# Weather_Station_For_Drones_-_MKR1000.net
KiCad netlist of a schematic drawn in EAGLE
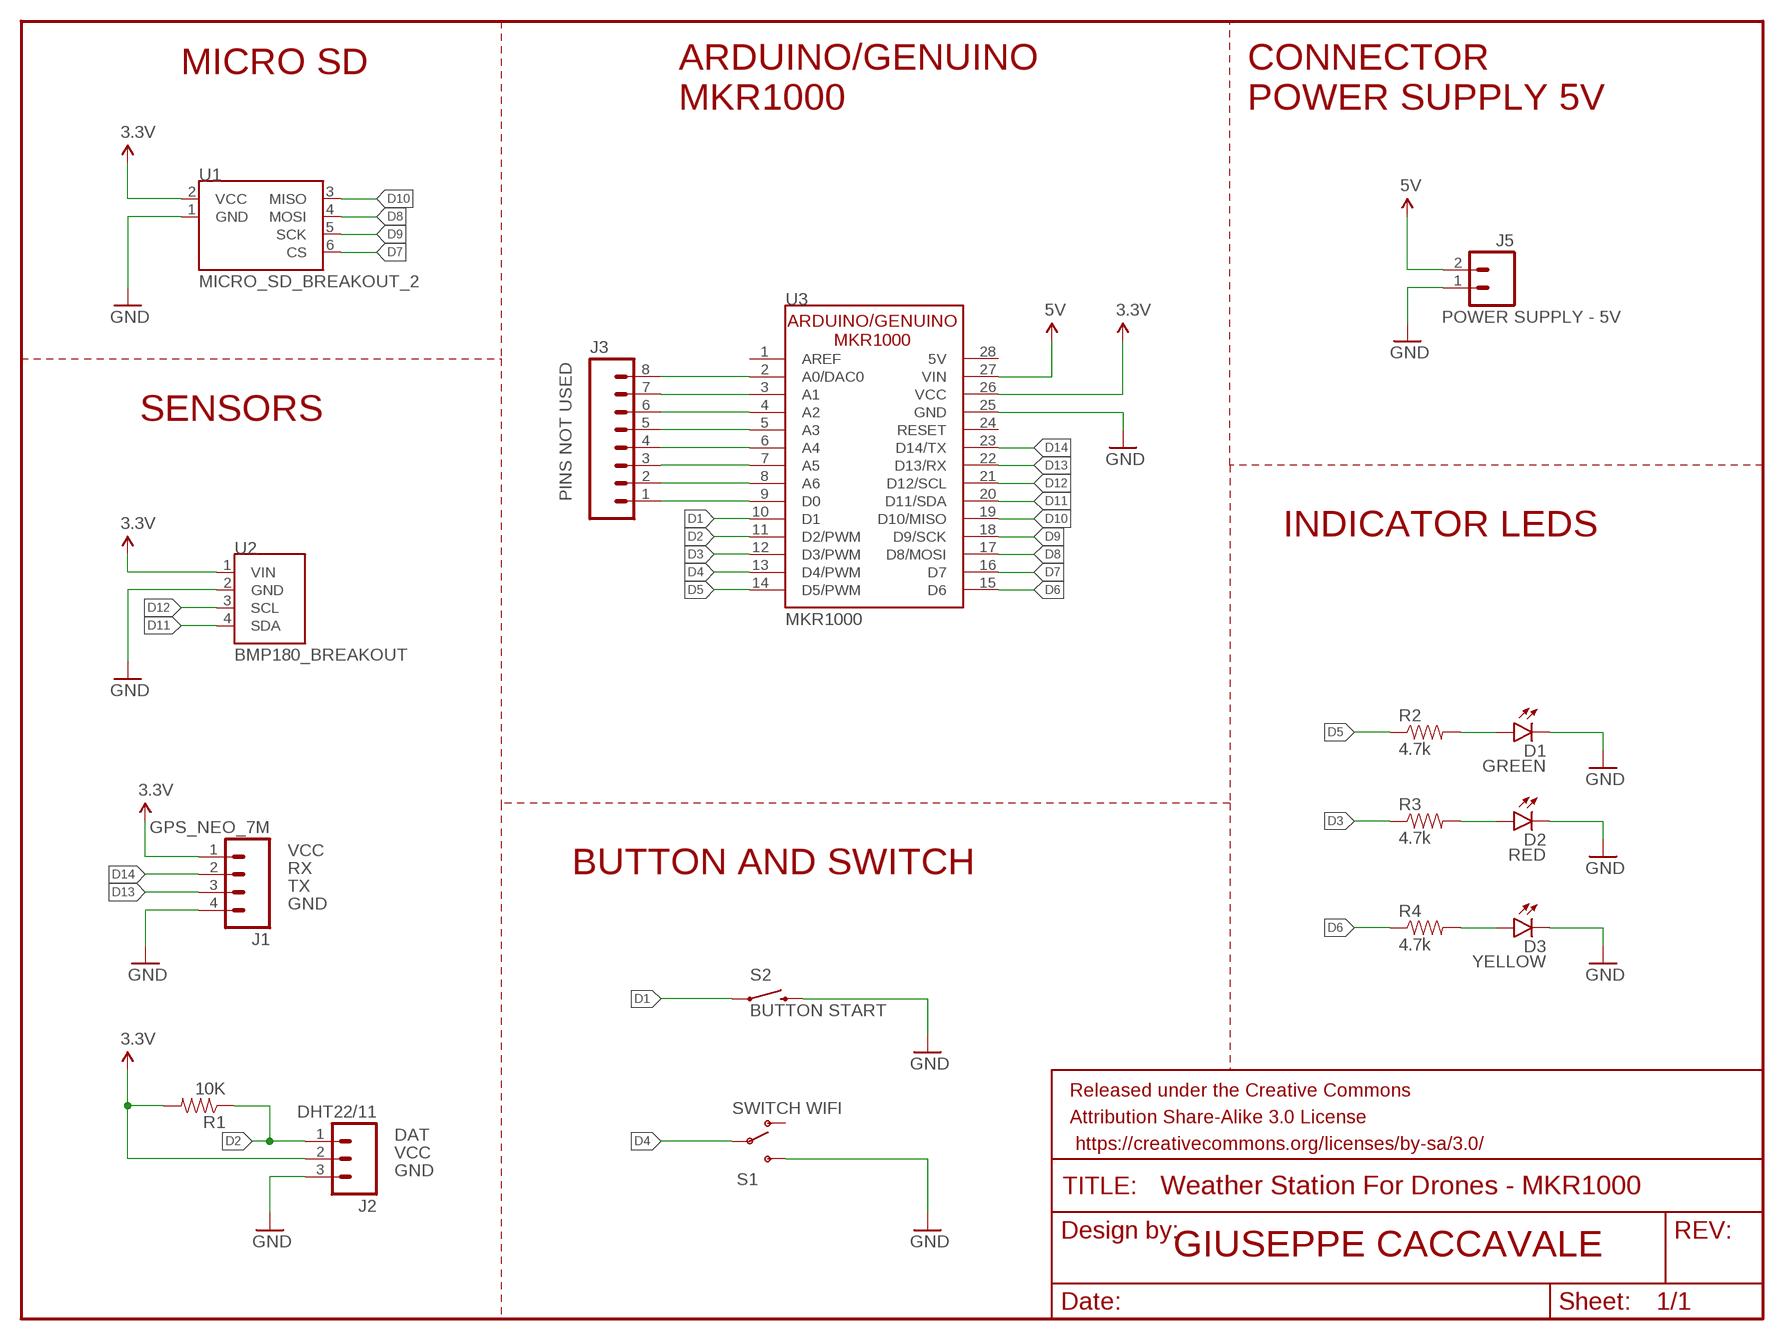
[diagram p0: schematic, sheet 1]

(export (version "E")
  (design (tool "Eeschema 10.0.6"))
  (components
    (comp (ref "D1")
      (value "GREEN")
      (footprint "eagle-import:LED3MM")
      (libsource (lib "eagle-import") (part "LED3MM"))
    )
    (comp (ref "D2")
      (value "RED")
      (footprint "eagle-import:LED3MM")
      (libsource (lib "eagle-import") (part "LED3MM"))
    )
    (comp (ref "D3")
      (value "YELLOW")
      (footprint "eagle-import:LED3MM")
      (libsource (lib "eagle-import") (part "LED3MM"))
    )
    (comp (ref "FRAME1")
      (value "FRAME-LETTER")
      (footprint "eagle-import:CREATIVE_COMMONS")
      (libsource (lib "eagle-import") (part "FRAME-LETTER"))
    )
    (comp (ref "J1")
      (value "GPS_NEO_7M")
      (footprint "eagle-import:1X04_LONGPADS")
      (libsource (lib "eagle-import") (part "M04LONGPADS"))
    )
    (comp (ref "J2")
      (value "DHT22/11")
      (footprint "eagle-import:1X03_LONGPADS")
      (libsource (lib "eagle-import") (part "M03LONGPADS"))
    )
    (comp (ref "J3")
      (value "PINS NOT USED")
      (footprint "eagle-import:1X08_LONGPADS")
      (libsource (lib "eagle-import") (part "M08LONGPADS"))
    )
    (comp (ref "J5")
      (value "POWER SUPPLY - 5V")
      (footprint "eagle-import:JST-2-PTH")
      (libsource (lib "eagle-import") (part "M02JST-PTH-2"))
    )
    (comp (ref "R1")
      (value "10K")
      (footprint "eagle-import:AXIAL-0.3")
      (libsource (lib "eagle-import") (part "RESISTORAXIAL-0.3"))
    )
    (comp (ref "R2")
      (value "4.7k")
      (footprint "eagle-import:AXIAL-0.3")
      (libsource (lib "eagle-import") (part "RESISTORAXIAL-0.3"))
    )
    (comp (ref "R3")
      (value "4.7k")
      (footprint "eagle-import:AXIAL-0.3")
      (libsource (lib "eagle-import") (part "RESISTORAXIAL-0.3"))
    )
    (comp (ref "R4")
      (value "4.7k")
      (footprint "eagle-import:AXIAL-0.3")
      (libsource (lib "eagle-import") (part "RESISTORAXIAL-0.3"))
    )
    (comp (ref "S1")
      (value "SWITCH WIFI")
      (footprint "eagle-import:SWITCH-SPDT_KIT")
      (libsource (lib "eagle-import") (part "SWITCH-SPDTKIT"))
    )
    (comp (ref "S2")
      (value "BUTTON START")
      (footprint "eagle-import:TACTILE-PTH")
      (libsource (lib "eagle-import") (part "SWITCH-MOMENTARY-2PTH"))
    )
    (comp (ref "U1")
      (value "MICRO_SD_BREAKOUT_2")
      (footprint "eagle-import:MICRO_SD_ONLY_PIN")
      (libsource (lib "eagle-import") (part "MICRO_SD_BREAKOUT_2"))
    )
    (comp (ref "U2")
      (value "BMP180_BREAKOUT")
      (footprint "eagle-import:BMP180_BREAKOUT")
      (libsource (lib "eagle-import") (part "BMP180_BREAKOUT"))
    )
    (comp (ref "U3")
      (value "MKR1000")
      (footprint "eagle-import:MKR1000")
      (libsource (lib "eagle-import") (part "MKR1000"))
    )
  )
  (nets
    (net (code "1") (name "3.3V") (class "Default")
      (node (ref "J1") (pin "1") (pinfunction "1_1") (pintype "passive"))
      (node (ref "J2") (pin "2") (pinfunction "2_2") (pintype "passive"))
      (node (ref "R1") (pin "P$2") (pinfunction "2_P$2") (pintype "passive"))
      (node (ref "U1") (pin "2") (pinfunction "VCC_2") (pintype "bidirectional"))
      (node (ref "U2") (pin "1") (pinfunction "VIN_1") (pintype "bidirectional"))
      (node (ref "U3") (pin "26") (pinfunction "VCC_26") (pintype "bidirectional"))
    )
    (net (code "2") (name "5V") (class "Default")
      (node (ref "J5") (pin "2") (pinfunction "2_2") (pintype "passive"))
      (node (ref "U3") (pin "27") (pinfunction "VIN_27") (pintype "bidirectional"))
    )
    (net (code "3") (name "D1") (class "Default")
      (node (ref "S2") (pin "1") (pinfunction "1_1") (pintype "passive"))
      (node (ref "S2") (pin "2") (pinfunction "1_2") (pintype "passive"))
      (node (ref "U3") (pin "10") (pinfunction "D1_10") (pintype "bidirectional"))
    )
    (net (code "4") (name "D2") (class "Default")
      (node (ref "J2") (pin "1") (pinfunction "1_1") (pintype "passive"))
      (node (ref "R1") (pin "P$1") (pinfunction "1_P$1") (pintype "passive"))
      (node (ref "U3") (pin "11") (pinfunction "D2/PWM_11") (pintype "bidirectional"))
    )
    (net (code "5") (name "D3") (class "Default")
      (node (ref "R3") (pin "P$1") (pinfunction "1_P$1") (pintype "passive"))
      (node (ref "U3") (pin "12") (pinfunction "D3/PWM_12") (pintype "bidirectional"))
    )
    (net (code "6") (name "D4") (class "Default")
      (node (ref "S1") (pin "2") (pinfunction "P_2") (pintype "passive"))
      (node (ref "U3") (pin "13") (pinfunction "D4/PWM_13") (pintype "bidirectional"))
    )
    (net (code "7") (name "D5") (class "Default")
      (node (ref "R2") (pin "P$1") (pinfunction "1_P$1") (pintype "passive"))
      (node (ref "U3") (pin "14") (pinfunction "D5/PWM_14") (pintype "bidirectional"))
    )
    (net (code "8") (name "D6") (class "Default")
      (node (ref "R4") (pin "P$1") (pinfunction "1_P$1") (pintype "passive"))
      (node (ref "U3") (pin "15") (pinfunction "D6_15") (pintype "bidirectional"))
    )
    (net (code "9") (name "D7") (class "Default")
      (node (ref "U1") (pin "6") (pinfunction "CS_6") (pintype "bidirectional"))
      (node (ref "U3") (pin "16") (pinfunction "D7_16") (pintype "bidirectional"))
    )
    (net (code "10") (name "D8") (class "Default")
      (node (ref "U1") (pin "4") (pinfunction "MOSI_4") (pintype "bidirectional"))
      (node (ref "U3") (pin "17") (pinfunction "D8/MOSI_17") (pintype "bidirectional"))
    )
    (net (code "11") (name "D9") (class "Default")
      (node (ref "U1") (pin "5") (pinfunction "SCK_5") (pintype "bidirectional"))
      (node (ref "U3") (pin "18") (pinfunction "D9/SCK_18") (pintype "bidirectional"))
    )
    (net (code "12") (name "D10") (class "Default")
      (node (ref "U1") (pin "3") (pinfunction "MISO_3") (pintype "bidirectional"))
      (node (ref "U3") (pin "19") (pinfunction "D10/MISO_19") (pintype "bidirectional"))
    )
    (net (code "13") (name "D11") (class "Default")
      (node (ref "U2") (pin "4") (pinfunction "SDA_4") (pintype "bidirectional"))
      (node (ref "U3") (pin "20") (pinfunction "D11/SDA_20") (pintype "bidirectional"))
    )
    (net (code "14") (name "D12") (class "Default")
      (node (ref "U2") (pin "3") (pinfunction "SCL_3") (pintype "bidirectional"))
      (node (ref "U3") (pin "21") (pinfunction "D12/SCL_21") (pintype "bidirectional"))
    )
    (net (code "15") (name "D13") (class "Default")
      (node (ref "J1") (pin "3") (pinfunction "3_3") (pintype "passive"))
      (node (ref "U3") (pin "22") (pinfunction "D13/RX_22") (pintype "bidirectional"))
    )
    (net (code "16") (name "D14") (class "Default")
      (node (ref "J1") (pin "2") (pinfunction "2_2") (pintype "passive"))
      (node (ref "U3") (pin "23") (pinfunction "D14/TX_23") (pintype "bidirectional"))
    )
    (net (code "17") (name "GND") (class "Default")
      (node (ref "D1") (pin "K") (pinfunction "C_K") (pintype "passive"))
      (node (ref "D2") (pin "K") (pinfunction "C_K") (pintype "passive"))
      (node (ref "D3") (pin "K") (pinfunction "C_K") (pintype "passive"))
      (node (ref "J1") (pin "4") (pinfunction "4_4") (pintype "passive"))
      (node (ref "J2") (pin "3") (pinfunction "3_3") (pintype "passive"))
      (node (ref "J5") (pin "1") (pinfunction "1_1") (pintype "passive"))
      (node (ref "S1") (pin "3") (pinfunction "S_3") (pintype "passive"))
      (node (ref "S2") (pin "3") (pinfunction "2_3") (pintype "passive"))
      (node (ref "S2") (pin "4") (pinfunction "2_4") (pintype "passive"))
      (node (ref "U1") (pin "1") (pinfunction "GND_1") (pintype "bidirectional"))
      (node (ref "U2") (pin "2") (pinfunction "GND_2") (pintype "bidirectional"))
      (node (ref "U3") (pin "25") (pinfunction "GND_25") (pintype "bidirectional"))
    )
    (net (code "18") (name "Net-(R2-2)") (class "Default")
      (node (ref "D1") (pin "A") (pinfunction "A_A") (pintype "passive"))
      (node (ref "R2") (pin "P$2") (pinfunction "2_P$2") (pintype "passive"))
    )
    (net (code "19") (name "Net-(R3-2)") (class "Default")
      (node (ref "D2") (pin "A") (pinfunction "A_A") (pintype "passive"))
      (node (ref "R3") (pin "P$2") (pinfunction "2_P$2") (pintype "passive"))
    )
    (net (code "20") (name "Net-(R4-2)") (class "Default")
      (node (ref "D3") (pin "A") (pinfunction "A_A") (pintype "passive"))
      (node (ref "R4") (pin "P$2") (pinfunction "2_P$2") (pintype "passive"))
    )
    (net (code "21") (name "Net-(U3-A0{slash}DAC0)") (class "Default")
      (node (ref "J3") (pin "8") (pinfunction "8_8") (pintype "passive"))
      (node (ref "U3") (pin "2") (pinfunction "A0/DAC0_2") (pintype "bidirectional"))
    )
    (net (code "22") (name "Net-(U3-A1)") (class "Default")
      (node (ref "J3") (pin "7") (pinfunction "7_7") (pintype "passive"))
      (node (ref "U3") (pin "3") (pinfunction "A1_3") (pintype "bidirectional"))
    )
    (net (code "23") (name "Net-(U3-A2)") (class "Default")
      (node (ref "J3") (pin "6") (pinfunction "6_6") (pintype "passive"))
      (node (ref "U3") (pin "4") (pinfunction "A2_4") (pintype "bidirectional"))
    )
    (net (code "24") (name "Net-(U3-A3)") (class "Default")
      (node (ref "J3") (pin "5") (pinfunction "5_5") (pintype "passive"))
      (node (ref "U3") (pin "5") (pinfunction "A3_5") (pintype "bidirectional"))
    )
    (net (code "25") (name "Net-(U3-A4)") (class "Default")
      (node (ref "J3") (pin "4") (pinfunction "4_4") (pintype "passive"))
      (node (ref "U3") (pin "6") (pinfunction "A4_6") (pintype "bidirectional"))
    )
    (net (code "26") (name "Net-(U3-A5)") (class "Default")
      (node (ref "J3") (pin "3") (pinfunction "3_3") (pintype "passive"))
      (node (ref "U3") (pin "7") (pinfunction "A5_7") (pintype "bidirectional"))
    )
    (net (code "27") (name "Net-(U3-A6)") (class "Default")
      (node (ref "J3") (pin "2") (pinfunction "2_2") (pintype "passive"))
      (node (ref "U3") (pin "8") (pinfunction "A6_8") (pintype "bidirectional"))
    )
    (net (code "28") (name "Net-(U3-D0)") (class "Default")
      (node (ref "J3") (pin "1") (pinfunction "1_1") (pintype "passive"))
      (node (ref "U3") (pin "9") (pinfunction "D0_9") (pintype "bidirectional"))
    )
    (net (code "29") (name "unconnected-(S1-O-Pad1)") (class "Default")
      (node (ref "S1") (pin "1") (pinfunction "O_1") (pintype "passive"))
    )
    (net (code "30") (name "unconnected-(U3-5V-Pad28)") (class "Default")
      (node (ref "U3") (pin "28") (pinfunction "5V_28") (pintype "bidirectional"))
    )
    (net (code "31") (name "unconnected-(U3-AREF-Pad1)") (class "Default")
      (node (ref "U3") (pin "1") (pinfunction "AREF_1") (pintype "bidirectional"))
    )
    (net (code "32") (name "unconnected-(U3-RESET-Pad24)") (class "Default")
      (node (ref "U3") (pin "24") (pinfunction "RESET_24") (pintype "bidirectional"))
    )
  )
)
